# DIOT_Backplane.net
KiCad netlist of a schematic drawn in Altium Designer
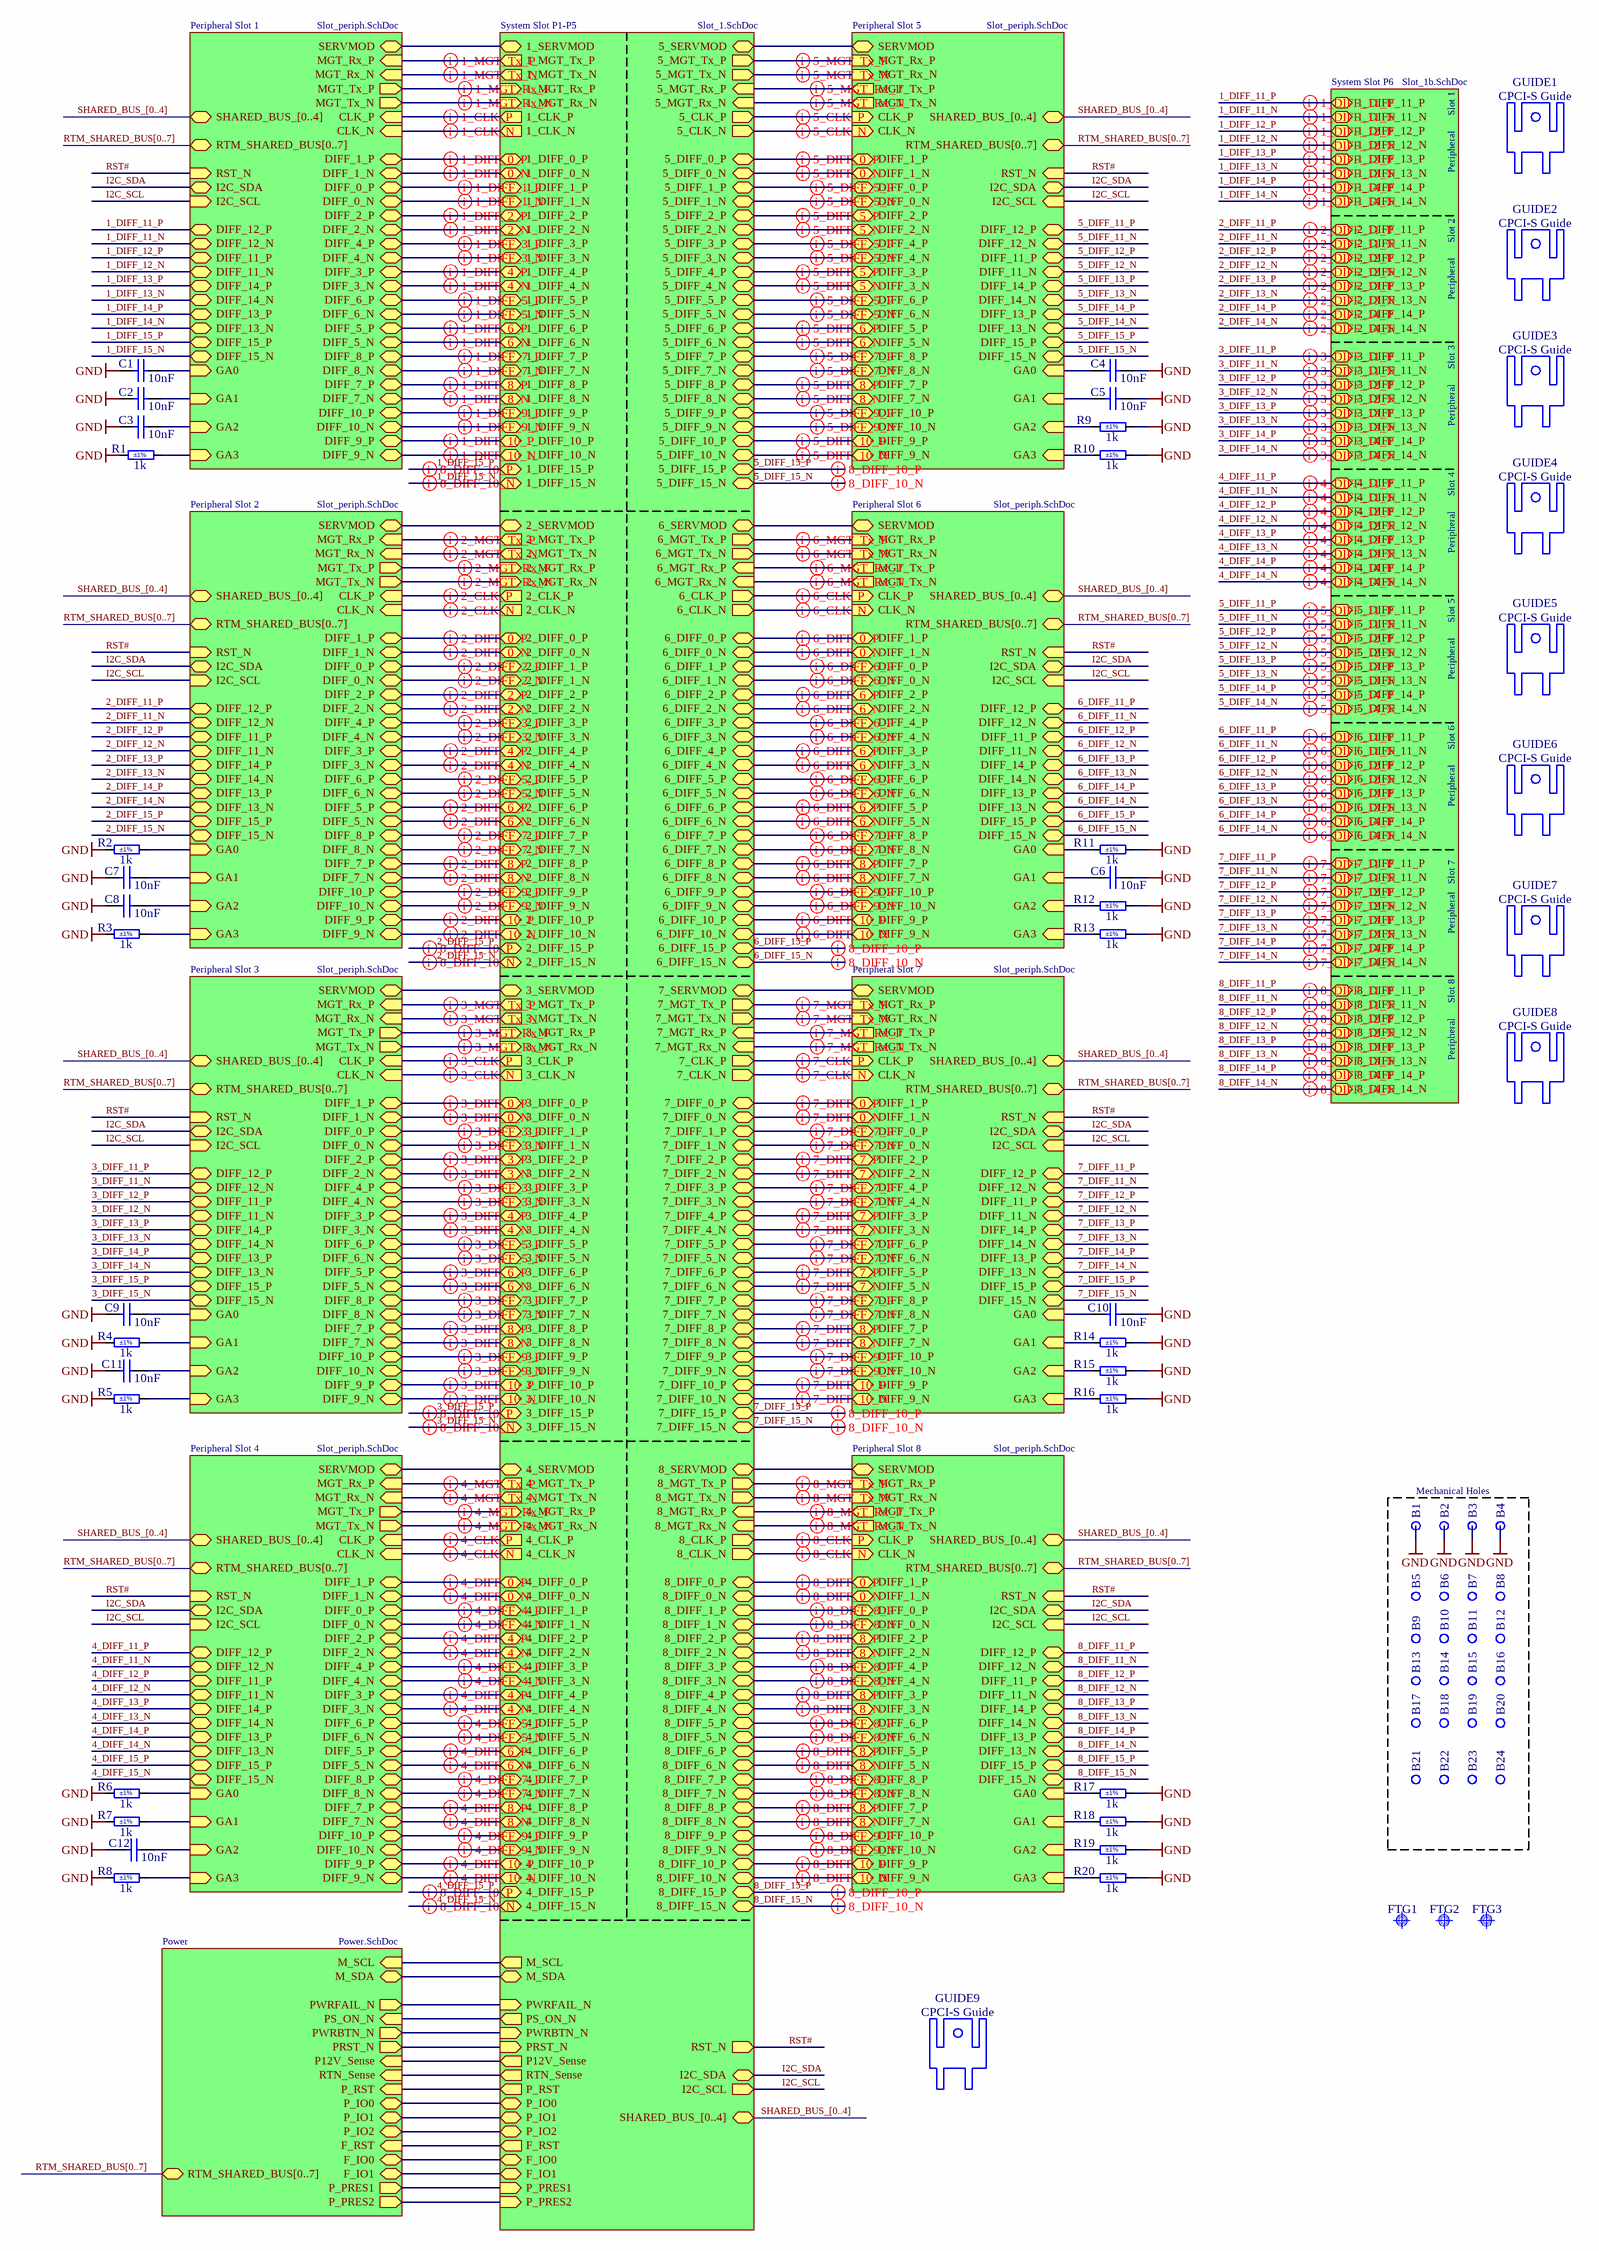
[diagram p0: DIOT_Backplane.SchDoc]

(export (version "E")
  (design (tool "Eeschema 10.0.6"))
  (components
    (comp (ref "B1")
      (value "Non Plated Hole")
      (footprint "MTG270_500_NPTH_8FCVIAS_BOTSM")
      (description "Single Terminal Socket")
      (fields
        (field (name "PART NUMBER") "NON-PLATED_HOLE2.7_PAD5.0_8FCVIAS_BOTSM")
        (field (name "AUTHOR") "CERN DEM WB")
      )
      (libsource (lib "Eletro-mechanical") (part "Single Terminal Socket"))
    )
    (comp (ref "B2")
      (value "Non Plated Hole")
      (footprint "MTG270_500_NPTH_8FCVIAS_BOTSM")
      (description "Single Terminal Socket")
      (fields
        (field (name "PART NUMBER") "NON-PLATED_HOLE2.7_PAD5.0_8FCVIAS_BOTSM")
        (field (name "AUTHOR") "CERN DEM WB")
      )
      (libsource (lib "Eletro-mechanical") (part "Single Terminal Socket"))
    )
    (comp (ref "B3")
      (value "Non Plated Hole")
      (footprint "MTG270_500_NPTH_8FCVIAS_BOTSM")
      (description "Single Terminal Socket")
      (fields
        (field (name "PART NUMBER") "NON-PLATED_HOLE2.7_PAD5.0_8FCVIAS_BOTSM")
        (field (name "AUTHOR") "CERN DEM WB")
      )
      (libsource (lib "Eletro-mechanical") (part "Single Terminal Socket"))
    )
    (comp (ref "B4")
      (value "Non Plated Hole")
      (footprint "MTG270_500_NPTH_8FCVIAS_BOTSM")
      (description "Single Terminal Socket")
      (fields
        (field (name "PART NUMBER") "NON-PLATED_HOLE2.7_PAD5.0_8FCVIAS_BOTSM")
        (field (name "AUTHOR") "CERN DEM WB")
      )
      (libsource (lib "Eletro-mechanical") (part "Single Terminal Socket"))
    )
    (comp (ref "B5")
      (value "Non Plated Hole")
      (footprint "MTG270")
      (description "Single Terminal Socket")
      (fields (field (name "PART NUMBER") "NON-PLATED_HOLE2.7") (field (name "AUTHOR") "CERN DEM BC"))
      (libsource (lib "Eletro-mechanical") (part "Single Terminal Socket"))
    )
    (comp (ref "B6")
      (value "Non Plated Hole")
      (footprint "MTG270")
      (description "Single Terminal Socket")
      (fields (field (name "PART NUMBER") "NON-PLATED_HOLE2.7") (field (name "AUTHOR") "CERN DEM BC"))
      (libsource (lib "Eletro-mechanical") (part "Single Terminal Socket"))
    )
    (comp (ref "B7")
      (value "Non Plated Hole")
      (footprint "MTG270")
      (description "Single Terminal Socket")
      (fields (field (name "PART NUMBER") "NON-PLATED_HOLE2.7") (field (name "AUTHOR") "CERN DEM BC"))
      (libsource (lib "Eletro-mechanical") (part "Single Terminal Socket"))
    )
    (comp (ref "B8")
      (value "Non Plated Hole")
      (footprint "MTG270")
      (description "Single Terminal Socket")
      (fields (field (name "PART NUMBER") "NON-PLATED_HOLE2.7") (field (name "AUTHOR") "CERN DEM BC"))
      (libsource (lib "Eletro-mechanical") (part "Single Terminal Socket"))
    )
    (comp (ref "B9")
      (value "Non Plated Hole")
      (footprint "MTG270")
      (description "Single Terminal Socket")
      (fields (field (name "PART NUMBER") "NON-PLATED_HOLE2.7") (field (name "AUTHOR") "CERN DEM BC"))
      (libsource (lib "Eletro-mechanical") (part "Single Terminal Socket"))
    )
    (comp (ref "B10")
      (value "Non Plated Hole")
      (footprint "MTG270")
      (description "Single Terminal Socket")
      (fields (field (name "PART NUMBER") "NON-PLATED_HOLE2.7") (field (name "AUTHOR") "CERN DEM BC"))
      (libsource (lib "Eletro-mechanical") (part "Single Terminal Socket"))
    )
    (comp (ref "B11")
      (value "Non Plated Hole")
      (footprint "MTG270")
      (description "Single Terminal Socket")
      (fields (field (name "PART NUMBER") "NON-PLATED_HOLE2.7") (field (name "AUTHOR") "CERN DEM BC"))
      (libsource (lib "Eletro-mechanical") (part "Single Terminal Socket"))
    )
    (comp (ref "B12")
      (value "Non Plated Hole")
      (footprint "MTG270")
      (description "Single Terminal Socket")
      (fields (field (name "PART NUMBER") "NON-PLATED_HOLE2.7") (field (name "AUTHOR") "CERN DEM BC"))
      (libsource (lib "Eletro-mechanical") (part "Single Terminal Socket"))
    )
    (comp (ref "B13")
      (value "Non Plated Hole")
      (footprint "MTG270")
      (description "Single Terminal Socket")
      (fields (field (name "PART NUMBER") "NON-PLATED_HOLE2.7") (field (name "AUTHOR") "CERN DEM BC"))
      (libsource (lib "Eletro-mechanical") (part "Single Terminal Socket"))
    )
    (comp (ref "B14")
      (value "Non Plated Hole")
      (footprint "MTG270")
      (description "Single Terminal Socket")
      (fields (field (name "PART NUMBER") "NON-PLATED_HOLE2.7") (field (name "AUTHOR") "CERN DEM BC"))
      (libsource (lib "Eletro-mechanical") (part "Single Terminal Socket"))
    )
    (comp (ref "B15")
      (value "Non Plated Hole")
      (footprint "MTG270")
      (description "Single Terminal Socket")
      (fields (field (name "PART NUMBER") "NON-PLATED_HOLE2.7") (field (name "AUTHOR") "CERN DEM BC"))
      (libsource (lib "Eletro-mechanical") (part "Single Terminal Socket"))
    )
    (comp (ref "B16")
      (value "Non Plated Hole")
      (footprint "MTG270")
      (description "Single Terminal Socket")
      (fields (field (name "PART NUMBER") "NON-PLATED_HOLE2.7") (field (name "AUTHOR") "CERN DEM BC"))
      (libsource (lib "Eletro-mechanical") (part "Single Terminal Socket"))
    )
    (comp (ref "B17")
      (value "Non Plated Hole")
      (footprint "MTG270")
      (description "Single Terminal Socket")
      (fields (field (name "PART NUMBER") "NON-PLATED_HOLE2.7") (field (name "AUTHOR") "CERN DEM BC"))
      (libsource (lib "Eletro-mechanical") (part "Single Terminal Socket"))
    )
    (comp (ref "B18")
      (value "Non Plated Hole")
      (footprint "MTG270")
      (description "Single Terminal Socket")
      (fields (field (name "PART NUMBER") "NON-PLATED_HOLE2.7") (field (name "AUTHOR") "CERN DEM BC"))
      (libsource (lib "Eletro-mechanical") (part "Single Terminal Socket"))
    )
    (comp (ref "B19")
      (value "Non Plated Hole")
      (footprint "MTG270")
      (description "Single Terminal Socket")
      (fields (field (name "PART NUMBER") "NON-PLATED_HOLE2.7") (field (name "AUTHOR") "CERN DEM BC"))
      (libsource (lib "Eletro-mechanical") (part "Single Terminal Socket"))
    )
    (comp (ref "B20")
      (value "Non Plated Hole")
      (footprint "MTG270")
      (description "Single Terminal Socket")
      (fields (field (name "PART NUMBER") "NON-PLATED_HOLE2.7") (field (name "AUTHOR") "CERN DEM BC"))
      (libsource (lib "Eletro-mechanical") (part "Single Terminal Socket"))
    )
    (comp (ref "B21")
      (value "Non Plated Hole")
      (footprint "MTG270")
      (description "Single Terminal Socket")
      (fields (field (name "PART NUMBER") "NON-PLATED_HOLE2.7") (field (name "AUTHOR") "CERN DEM BC"))
      (libsource (lib "Eletro-mechanical") (part "Single Terminal Socket"))
    )
    (comp (ref "B22")
      (value "Non Plated Hole")
      (footprint "MTG270")
      (description "Single Terminal Socket")
      (fields (field (name "PART NUMBER") "NON-PLATED_HOLE2.7") (field (name "AUTHOR") "CERN DEM BC"))
      (libsource (lib "Eletro-mechanical") (part "Single Terminal Socket"))
    )
    (comp (ref "B23")
      (value "Non Plated Hole")
      (footprint "MTG270")
      (description "Single Terminal Socket")
      (fields (field (name "PART NUMBER") "NON-PLATED_HOLE2.7") (field (name "AUTHOR") "CERN DEM BC"))
      (libsource (lib "Eletro-mechanical") (part "Single Terminal Socket"))
    )
    (comp (ref "B24")
      (value "Non Plated Hole")
      (footprint "MTG270")
      (description "Single Terminal Socket")
      (fields (field (name "PART NUMBER") "NON-PLATED_HOLE2.7") (field (name "AUTHOR") "CERN DEM BC"))
      (libsource (lib "Eletro-mechanical") (part "Single Terminal Socket"))
    )
    (comp (ref "C1")
      (value "10nF")
      (footprint "CAPC1005X55N")
      (description "Non-polarised capacitor")
      (fields
        (field (name "PART NUMBER") "CC0402_10NF_16V_10%_X7R")
        (field (name "VOLTAGE") "16V")
        (field (name "AUTHOR") "CERN DEM JLC")
      )
      (libsource (lib "Capacitors") (part "Capacitor - non polarized"))
    )
    (comp (ref "C2")
      (value "10nF")
      (footprint "CAPC1005X55N")
      (description "Non-polarised capacitor")
      (fields
        (field (name "PART NUMBER") "CC0402_10NF_16V_10%_X7R")
        (field (name "VOLTAGE") "16V")
        (field (name "AUTHOR") "CERN DEM JLC")
      )
      (libsource (lib "Capacitors") (part "Capacitor - non polarized"))
    )
    (comp (ref "C3")
      (value "10nF")
      (footprint "CAPC1005X55N")
      (description "Non-polarised capacitor")
      (fields
        (field (name "PART NUMBER") "CC0402_10NF_16V_10%_X7R")
        (field (name "VOLTAGE") "16V")
        (field (name "AUTHOR") "CERN DEM JLC")
      )
      (libsource (lib "Capacitors") (part "Capacitor - non polarized"))
    )
    (comp (ref "C4")
      (value "10nF")
      (footprint "CAPC1005X55N")
      (description "Non-polarised capacitor")
      (fields
        (field (name "PART NUMBER") "CC0402_10NF_16V_10%_X7R")
        (field (name "VOLTAGE") "16V")
        (field (name "AUTHOR") "CERN DEM JLC")
      )
      (libsource (lib "Capacitors") (part "Capacitor - non polarized"))
    )
    (comp (ref "C5")
      (value "10nF")
      (footprint "CAPC1005X55N")
      (description "Non-polarised capacitor")
      (fields
        (field (name "PART NUMBER") "CC0402_10NF_16V_10%_X7R")
        (field (name "VOLTAGE") "16V")
        (field (name "AUTHOR") "CERN DEM JLC")
      )
      (libsource (lib "Capacitors") (part "Capacitor - non polarized"))
    )
    (comp (ref "C6")
      (value "10nF")
      (footprint "CAPC1005X55N")
      (description "Non-polarised capacitor")
      (fields
        (field (name "PART NUMBER") "CC0402_10NF_16V_10%_X7R")
        (field (name "VOLTAGE") "16V")
        (field (name "AUTHOR") "CERN DEM JLC")
      )
      (libsource (lib "Capacitors") (part "Capacitor - non polarized"))
    )
    (comp (ref "C7")
      (value "10nF")
      (footprint "CAPC1005X55N")
      (description "Non-polarised capacitor")
      (fields
        (field (name "PART NUMBER") "CC0402_10NF_16V_10%_X7R")
        (field (name "VOLTAGE") "16V")
        (field (name "AUTHOR") "CERN DEM JLC")
      )
      (libsource (lib "Capacitors") (part "Capacitor - non polarized"))
    )
    (comp (ref "C8")
      (value "10nF")
      (footprint "CAPC1005X55N")
      (description "Non-polarised capacitor")
      (fields
        (field (name "PART NUMBER") "CC0402_10NF_16V_10%_X7R")
        (field (name "VOLTAGE") "16V")
        (field (name "AUTHOR") "CERN DEM JLC")
      )
      (libsource (lib "Capacitors") (part "Capacitor - non polarized"))
    )
    (comp (ref "C9")
      (value "10nF")
      (footprint "CAPC1005X55N")
      (description "Non-polarised capacitor")
      (fields
        (field (name "PART NUMBER") "CC0402_10NF_16V_10%_X7R")
        (field (name "VOLTAGE") "16V")
        (field (name "AUTHOR") "CERN DEM JLC")
      )
      (libsource (lib "Capacitors") (part "Capacitor - non polarized"))
    )
    (comp (ref "C10")
      (value "10nF")
      (footprint "CAPC1005X55N")
      (description "Non-polarised capacitor")
      (fields
        (field (name "PART NUMBER") "CC0402_10NF_16V_10%_X7R")
        (field (name "VOLTAGE") "16V")
        (field (name "AUTHOR") "CERN DEM JLC")
      )
      (libsource (lib "Capacitors") (part "Capacitor - non polarized"))
    )
    (comp (ref "C11")
      (value "10nF")
      (footprint "CAPC1005X55N")
      (description "Non-polarised capacitor")
      (fields
        (field (name "PART NUMBER") "CC0402_10NF_16V_10%_X7R")
        (field (name "VOLTAGE") "16V")
        (field (name "AUTHOR") "CERN DEM JLC")
      )
      (libsource (lib "Capacitors") (part "Capacitor - non polarized"))
    )
    (comp (ref "C12")
      (value "10nF")
      (footprint "CAPC1005X55N")
      (description "Non-polarised capacitor")
      (fields
        (field (name "PART NUMBER") "CC0402_10NF_16V_10%_X7R")
        (field (name "VOLTAGE") "16V")
        (field (name "AUTHOR") "CERN DEM JLC")
      )
      (libsource (lib "Capacitors") (part "Capacitor - non polarized"))
    )
    (comp (ref "FTG1")
      (value "Use only in PCB")
      (footprint "FIDUCIAL_TOP_C100-200")
      (description "Fiducial Target")
      (fields (field (name "PART NUMBER") "FIDUCIAL_TARGET_C100-200") (field (name "AUTHOR") "CERN DEM JLC"))
      (libsource (lib "Eletro-mechanical") (part "Fiducial Target"))
    )
    (comp (ref "FTG2")
      (value "Use only in PCB")
      (footprint "FIDUCIAL_TOP_C100-200")
      (description "Fiducial Target")
      (fields (field (name "PART NUMBER") "FIDUCIAL_TARGET_C100-200") (field (name "AUTHOR") "CERN DEM JLC"))
      (libsource (lib "Eletro-mechanical") (part "Fiducial Target"))
    )
    (comp (ref "FTG3")
      (value "Use only in PCB")
      (footprint "FIDUCIAL_TOP_C100-200")
      (description "Fiducial Target")
      (fields (field (name "PART NUMBER") "FIDUCIAL_TARGET_C100-200") (field (name "AUTHOR") "CERN DEM JLC"))
      (libsource (lib "Eletro-mechanical") (part "Fiducial Target"))
    )
    (comp (ref "GUIDE1")
      (value "CPCI-S Guide")
      (footprint "EDA-04126-V1-0")
      (description "PICMG CompactPCI Serial Backplane Guide Element")
      (fields
        (field (name "PART NUMBER") "EDA-04126-V1-0")
        (field (name "MANUFACTURER") "CERN")
        (field (name "AUTHOR") "CERN DEM BC")
      )
      (libsource (lib "Eletro-mechanical") (part "CPCI-S Guide"))
    )
    (comp (ref "GUIDE2")
      (value "CPCI-S Guide")
      (footprint "EDA-04126-V1-0")
      (description "PICMG CompactPCI Serial Backplane Guide Element")
      (fields
        (field (name "PART NUMBER") "EDA-04126-V1-0")
        (field (name "MANUFACTURER") "CERN")
        (field (name "AUTHOR") "CERN DEM BC")
      )
      (libsource (lib "Eletro-mechanical") (part "CPCI-S Guide"))
    )
    (comp (ref "GUIDE3")
      (value "CPCI-S Guide")
      (footprint "EDA-04126-V1-0")
      (description "PICMG CompactPCI Serial Backplane Guide Element")
      (fields
        (field (name "PART NUMBER") "EDA-04126-V1-0")
        (field (name "MANUFACTURER") "CERN")
        (field (name "AUTHOR") "CERN DEM BC")
      )
      (libsource (lib "Eletro-mechanical") (part "CPCI-S Guide"))
    )
    (comp (ref "GUIDE4")
      (value "CPCI-S Guide")
      (footprint "EDA-04126-V1-0")
      (description "PICMG CompactPCI Serial Backplane Guide Element")
      (fields
        (field (name "PART NUMBER") "EDA-04126-V1-0")
        (field (name "MANUFACTURER") "CERN")
        (field (name "AUTHOR") "CERN DEM BC")
      )
      (libsource (lib "Eletro-mechanical") (part "CPCI-S Guide"))
    )
    (comp (ref "GUIDE5")
      (value "CPCI-S Guide")
      (footprint "EDA-04126-V1-0")
      (description "PICMG CompactPCI Serial Backplane Guide Element")
      (fields
        (field (name "PART NUMBER") "EDA-04126-V1-0")
        (field (name "MANUFACTURER") "CERN")
        (field (name "AUTHOR") "CERN DEM BC")
      )
      (libsource (lib "Eletro-mechanical") (part "CPCI-S Guide"))
    )
    (comp (ref "GUIDE6")
      (value "CPCI-S Guide")
      (footprint "EDA-04126-V1-0")
      (description "PICMG CompactPCI Serial Backplane Guide Element")
      (fields
        (field (name "PART NUMBER") "EDA-04126-V1-0")
        (field (name "MANUFACTURER") "CERN")
        (field (name "AUTHOR") "CERN DEM BC")
      )
      (libsource (lib "Eletro-mechanical") (part "CPCI-S Guide"))
    )
    (comp (ref "GUIDE7")
      (value "CPCI-S Guide")
      (footprint "EDA-04126-V1-0")
      (description "PICMG CompactPCI Serial Backplane Guide Element")
      (fields
        (field (name "PART NUMBER") "EDA-04126-V1-0")
        (field (name "MANUFACTURER") "CERN")
        (field (name "AUTHOR") "CERN DEM BC")
      )
      (libsource (lib "Eletro-mechanical") (part "CPCI-S Guide"))
    )
    (comp (ref "GUIDE8")
      (value "CPCI-S Guide")
      (footprint "EDA-04126-V1-0")
      (description "PICMG CompactPCI Serial Backplane Guide Element")
      (fields
        (field (name "PART NUMBER") "EDA-04126-V1-0")
        (field (name "MANUFACTURER") "CERN")
        (field (name "AUTHOR") "CERN DEM BC")
      )
      (libsource (lib "Eletro-mechanical") (part "CPCI-S Guide"))
    )
    (comp (ref "GUIDE9")
      (value "CPCI-S Guide")
      (footprint "EDA-04126-V1-0")
      (description "PICMG CompactPCI Serial Backplane Guide Element")
      (fields
        (field (name "PART NUMBER") "EDA-04126-V1-0")
        (field (name "MANUFACTURER") "CERN")
        (field (name "AUTHOR") "CERN DEM BC")
      )
      (libsource (lib "Eletro-mechanical") (part "CPCI-S Guide"))
    )
    (comp (ref "R1")
      (value "1k")
      (footprint "RESC1005X40N")
      (description "Resistor - 1%")
      (fields
        (field (name "TOLERANCE") "±1%")
        (field (name "PART NUMBER") "R0402_1K_1%_0.0625W_100PPM")
        (field (name "POWER") "0.0625W")
        (field (name "AUTHOR") "CERN DEM JLC")
      )
      (libsource (lib "Resistors") (part "Resistor - 1%"))
    )
    (comp (ref "R2")
      (value "1k")
      (footprint "RESC1005X40N")
      (description "Resistor - 1%")
      (fields
        (field (name "TOLERANCE") "±1%")
        (field (name "PART NUMBER") "R0402_1K_1%_0.0625W_100PPM")
        (field (name "POWER") "0.0625W")
        (field (name "AUTHOR") "CERN DEM JLC")
      )
      (libsource (lib "Resistors") (part "Resistor - 1%"))
    )
    (comp (ref "R3")
      (value "1k")
      (footprint "RESC1005X40N")
      (description "Resistor - 1%")
      (fields
        (field (name "TOLERANCE") "±1%")
        (field (name "PART NUMBER") "R0402_1K_1%_0.0625W_100PPM")
        (field (name "POWER") "0.0625W")
        (field (name "AUTHOR") "CERN DEM JLC")
      )
      (libsource (lib "Resistors") (part "Resistor - 1%"))
    )
    (comp (ref "R4")
      (value "1k")
      (footprint "RESC1005X40N")
      (description "Resistor - 1%")
      (fields
        (field (name "TOLERANCE") "±1%")
        (field (name "PART NUMBER") "R0402_1K_1%_0.0625W_100PPM")
        (field (name "POWER") "0.0625W")
        (field (name "AUTHOR") "CERN DEM JLC")
      )
      (libsource (lib "Resistors") (part "Resistor - 1%"))
    )
    (comp (ref "R5")
      (value "1k")
      (footprint "RESC1005X40N")
      (description "Resistor - 1%")
      (fields
        (field (name "TOLERANCE") "±1%")
        (field (name "PART NUMBER") "R0402_1K_1%_0.0625W_100PPM")
        (field (name "POWER") "0.0625W")
        (field (name "AUTHOR") "CERN DEM JLC")
      )
      (libsource (lib "Resistors") (part "Resistor - 1%"))
    )
    (comp (ref "R6")
      (value "1k")
      (footprint "RESC1005X40N")
      (description "Resistor - 1%")
      (fields
        (field (name "TOLERANCE") "±1%")
        (field (name "PART NUMBER") "R0402_1K_1%_0.0625W_100PPM")
        (field (name "POWER") "0.0625W")
        (field (name "AUTHOR") "CERN DEM JLC")
      )
      (libsource (lib "Resistors") (part "Resistor - 1%"))
    )
    (comp (ref "R7")
      (value "1k")
      (footprint "RESC1005X40N")
      (description "Resistor - 1%")
      (fields
        (field (name "TOLERANCE") "±1%")
        (field (name "PART NUMBER") "R0402_1K_1%_0.0625W_100PPM")
        (field (name "POWER") "0.0625W")
        (field (name "AUTHOR") "CERN DEM JLC")
      )
      (libsource (lib "Resistors") (part "Resistor - 1%"))
    )
    (comp (ref "R8")
      (value "1k")
      (footprint "RESC1005X40N")
      (description "Resistor - 1%")
      (fields
        (field (name "TOLERANCE") "±1%")
        (field (name "PART NUMBER") "R0402_1K_1%_0.0625W_100PPM")
        (field (name "POWER") "0.0625W")
        (field (name "AUTHOR") "CERN DEM JLC")
      )
      (libsource (lib "Resistors") (part "Resistor - 1%"))
    )
    (comp (ref "R9")
      (value "1k")
      (footprint "RESC1005X40N")
      (description "Resistor - 1%")
      (fields
        (field (name "TOLERANCE") "±1%")
        (field (name "PART NUMBER") "R0402_1K_1%_0.0625W_100PPM")
        (field (name "POWER") "0.0625W")
        (field (name "AUTHOR") "CERN DEM JLC")
      )
      (libsource (lib "Resistors") (part "Resistor - 1%"))
    )
    (comp (ref "R10")
      (value "1k")
      (footprint "RESC1005X40N")
      (description "Resistor - 1%")
      (fields
        (field (name "TOLERANCE") "±1%")
        (field (name "PART NUMBER") "R0402_1K_1%_0.0625W_100PPM")
        (field (name "POWER") "0.0625W")
        (field (name "AUTHOR") "CERN DEM JLC")
      )
      (libsource (lib "Resistors") (part "Resistor - 1%"))
    )
    (comp (ref "R11")
      (value "1k")
      (footprint "RESC1005X40N")
      (description "Resistor - 1%")
      (fields
        (field (name "TOLERANCE") "±1%")
        (field (name "PART NUMBER") "R0402_1K_1%_0.0625W_100PPM")
        (field (name "POWER") "0.0625W")
        (field (name "AUTHOR") "CERN DEM JLC")
      )
      (libsource (lib "Resistors") (part "Resistor - 1%"))
    )
    (comp (ref "R12")
      (value "1k")
      (footprint "RESC1005X40N")
      (description "Resistor - 1%")
      (fields
        (field (name "TOLERANCE") "±1%")
        (field (name "PART NUMBER") "R0402_1K_1%_0.0625W_100PPM")
        (field (name "POWER") "0.0625W")
        (field (name "AUTHOR") "CERN DEM JLC")
      )
      (libsource (lib "Resistors") (part "Resistor - 1%"))
    )
    (comp (ref "R13")
      (value "1k")
      (footprint "RESC1005X40N")
      (description "Resistor - 1%")
      (fields
        (field (name "TOLERANCE") "±1%")
        (field (name "PART NUMBER") "R0402_1K_1%_0.0625W_100PPM")
        (field (name "POWER") "0.0625W")
        (field (name "AUTHOR") "CERN DEM JLC")
      )
      (libsource (lib "Resistors") (part "Resistor - 1%"))
    )
    (comp (ref "R14")
      (value "1k")
      (footprint "RESC1005X40N")
      (description "Resistor - 1%")
      (fields
        (field (name "TOLERANCE") "±1%")
        (field (name "PART NUMBER") "R0402_1K_1%_0.0625W_100PPM")
        (field (name "POWER") "0.0625W")
        (field (name "AUTHOR") "CERN DEM JLC")
      )
      (libsource (lib "Resistors") (part "Resistor - 1%"))
    )
    (comp (ref "R15")
      (value "1k")
      (footprint "RESC1005X40N")
      (description "Resistor - 1%")
      (fields
        (field (name "TOLERANCE") "±1%")
        (field (name "PART NUMBER") "R0402_1K_1%_0.0625W_100PPM")
        (field (name "POWER") "0.0625W")
        (field (name "AUTHOR") "CERN DEM JLC")
      )
      (libsource (lib "Resistors") (part "Resistor - 1%"))
    )
    (comp (ref "R16")
      (value "1k")
      (footprint "RESC1005X40N")
      (description "Resistor - 1%")
      (fields
        (field (name "TOLERANCE") "±1%")
        (field (name "PART NUMBER") "R0402_1K_1%_0.0625W_100PPM")
        (field (name "POWER") "0.0625W")
        (field (name "AUTHOR") "CERN DEM JLC")
      )
      (libsource (lib "Resistors") (part "Resistor - 1%"))
    )
    (comp (ref "R17")
      (value "1k")
      (footprint "RESC1005X40N")
      (description "Resistor - 1%")
      (fields
        (field (name "TOLERANCE") "±1%")
        (field (name "PART NUMBER") "R0402_1K_1%_0.0625W_100PPM")
        (field (name "POWER") "0.0625W")
        (field (name "AUTHOR") "CERN DEM JLC")
      )
      (libsource (lib "Resistors") (part "Resistor - 1%"))
    )
    (comp (ref "R18")
      (value "1k")
      (footprint "RESC1005X40N")
      (description "Resistor - 1%")
      (fields
        (field (name "TOLERANCE") "±1%")
        (field (name "PART NUMBER") "R0402_1K_1%_0.0625W_100PPM")
        (field (name "POWER") "0.0625W")
        (field (name "AUTHOR") "CERN DEM JLC")
      )
      (libsource (lib "Resistors") (part "Resistor - 1%"))
    )
    (comp (ref "R19")
      (value "1k")
      (footprint "RESC1005X40N")
      (description "Resistor - 1%")
      (fields
        (field (name "TOLERANCE") "±1%")
        (field (name "PART NUMBER") "R0402_1K_1%_0.0625W_100PPM")
        (field (name "POWER") "0.0625W")
        (field (name "AUTHOR") "CERN DEM JLC")
      )
      (libsource (lib "Resistors") (part "Resistor - 1%"))
    )
    (comp (ref "R20")
      (value "1k")
      (footprint "RESC1005X40N")
      (description "Resistor - 1%")
      (fields
        (field (name "TOLERANCE") "±1%")
        (field (name "PART NUMBER") "R0402_1K_1%_0.0625W_100PPM")
        (field (name "POWER") "0.0625W")
        (field (name "AUTHOR") "CERN DEM JLC")
      )
      (libsource (lib "Resistors") (part "Resistor - 1%"))
    )
  )
  (nets
    (net (code "313") (name "/GA0") (class "Default")
      (node (ref "C1") (pin "2") (pinfunction "2_2") (pintype "passive"))
    )
    (net (code "314") (name "/GA0_1") (class "Default")
      (node (ref "R17") (pin "1") (pinfunction "1_1") (pintype "passive"))
    )
    (net (code "315") (name "/GA0_2") (class "Default")
      (node (ref "R2") (pin "2") (pinfunction "2_2") (pintype "passive"))
    )
    (net (code "316") (name "/GA0_3") (class "Default")
      (node (ref "R6") (pin "2") (pinfunction "2_2") (pintype "passive"))
    )
    (net (code "317") (name "/GA0_4") (class "Default")
      (node (ref "C9") (pin "2") (pinfunction "2_2") (pintype "passive"))
    )
    (net (code "318") (name "/GA0_5") (class "Default")
      (node (ref "C4") (pin "1") (pinfunction "1_1") (pintype "passive"))
    )
    (net (code "319") (name "/GA0_6") (class "Default")
      (node (ref "R11") (pin "1") (pinfunction "1_1") (pintype "passive"))
    )
    (net (code "320") (name "/GA0_7") (class "Default")
      (node (ref "C10") (pin "1") (pinfunction "1_1") (pintype "passive"))
    )
    (net (code "321") (name "/GA1") (class "Default")
      (node (ref "C2") (pin "2") (pinfunction "2_2") (pintype "passive"))
    )
    (net (code "322") (name "/GA1_1") (class "Default")
      (node (ref "R18") (pin "1") (pinfunction "1_1") (pintype "passive"))
    )
    (net (code "323") (name "/GA1_2") (class "Default")
      (node (ref "C7") (pin "2") (pinfunction "2_2") (pintype "passive"))
    )
    (net (code "324") (name "/GA1_3") (class "Default")
      (node (ref "R7") (pin "2") (pinfunction "2_2") (pintype "passive"))
    )
    (net (code "325") (name "/GA1_4") (class "Default")
      (node (ref "R4") (pin "2") (pinfunction "2_2") (pintype "passive"))
    )
    (net (code "326") (name "/GA1_5") (class "Default")
      (node (ref "C5") (pin "1") (pinfunction "1_1") (pintype "passive"))
    )
    (net (code "327") (name "/GA1_6") (class "Default")
      (node (ref "C6") (pin "1") (pinfunction "1_1") (pintype "passive"))
    )
    (net (code "328") (name "/GA1_7") (class "Default")
      (node (ref "R14") (pin "1") (pinfunction "1_1") (pintype "passive"))
    )
    (net (code "329") (name "/GA2") (class "Default")
      (node (ref "C3") (pin "2") (pinfunction "2_2") (pintype "passive"))
    )
    (net (code "330") (name "/GA2_1") (class "Default")
      (node (ref "R19") (pin "1") (pinfunction "1_1") (pintype "passive"))
    )
    (net (code "331") (name "/GA2_2") (class "Default")
      (node (ref "C8") (pin "2") (pinfunction "2_2") (pintype "passive"))
    )
    (net (code "332") (name "/GA2_3") (class "Default")
      (node (ref "C12") (pin "2") (pinfunction "2_2") (pintype "passive"))
    )
    (net (code "333") (name "/GA2_4") (class "Default")
      (node (ref "C11") (pin "2") (pinfunction "2_2") (pintype "passive"))
    )
    (net (code "334") (name "/GA2_5") (class "Default")
      (node (ref "R9") (pin "1") (pinfunction "1_1") (pintype "passive"))
    )
    (net (code "335") (name "/GA2_6") (class "Default")
      (node (ref "R12") (pin "1") (pinfunction "1_1") (pintype "passive"))
    )
    (net (code "336") (name "/GA2_7") (class "Default")
      (node (ref "R15") (pin "1") (pinfunction "1_1") (pintype "passive"))
    )
    (net (code "337") (name "/GA3") (class "Default")
      (node (ref "R1") (pin "2") (pinfunction "2_2") (pintype "passive"))
    )
    (net (code "338") (name "/GA3_1") (class "Default")
      (node (ref "R20") (pin "1") (pinfunction "1_1") (pintype "passive"))
    )
    (net (code "339") (name "/GA3_2") (class "Default")
      (node (ref "R3") (pin "2") (pinfunction "2_2") (pintype "passive"))
    )
    (net (code "340") (name "/GA3_3") (class "Default")
      (node (ref "R8") (pin "2") (pinfunction "2_2") (pintype "passive"))
    )
    (net (code "341") (name "/GA3_4") (class "Default")
      (node (ref "R5") (pin "2") (pinfunction "2_2") (pintype "passive"))
    )
    (net (code "342") (name "/GA3_5") (class "Default")
      (node (ref "R10") (pin "1") (pinfunction "1_1") (pintype "passive"))
    )
    (net (code "343") (name "/GA3_6") (class "Default")
      (node (ref "R13") (pin "1") (pinfunction "1_1") (pintype "passive"))
    )
    (net (code "344") (name "/GA3_7") (class "Default")
      (node (ref "R16") (pin "1") (pinfunction "1_1") (pintype "passive"))
    )
    (net (code "380") (name "GND") (class "Default")
      (node (ref "B1") (pin "1") (pinfunction "1_1") (pintype "bidirectional"))
      (node (ref "B2") (pin "1") (pinfunction "1_1") (pintype "bidirectional"))
      (node (ref "B3") (pin "1") (pinfunction "1_1") (pintype "bidirectional"))
      (node (ref "B4") (pin "1") (pinfunction "1_1") (pintype "bidirectional"))
      (node (ref "C1") (pin "1") (pinfunction "1_1") (pintype "passive"))
      (node (ref "C10") (pin "2") (pinfunction "2_2") (pintype "passive"))
      (node (ref "C11") (pin "1") (pinfunction "1_1") (pintype "passive"))
      (node (ref "C12") (pin "1") (pinfunction "1_1") (pintype "passive"))
      (node (ref "C2") (pin "1") (pinfunction "1_1") (pintype "passive"))
      (node (ref "C3") (pin "1") (pinfunction "1_1") (pintype "passive"))
      (node (ref "C4") (pin "2") (pinfunction "2_2") (pintype "passive"))
      (node (ref "C5") (pin "2") (pinfunction "2_2") (pintype "passive"))
      (node (ref "C6") (pin "2") (pinfunction "2_2") (pintype "passive"))
      (node (ref "C7") (pin "1") (pinfunction "1_1") (pintype "passive"))
      (node (ref "C8") (pin "1") (pinfunction "1_1") (pintype "passive"))
      (node (ref "C9") (pin "1") (pinfunction "1_1") (pintype "passive"))
      (node (ref "R1") (pin "1") (pinfunction "1_1") (pintype "passive"))
      (node (ref "R10") (pin "2") (pinfunction "2_2") (pintype "passive"))
      (node (ref "R11") (pin "2") (pinfunction "2_2") (pintype "passive"))
      (node (ref "R12") (pin "2") (pinfunction "2_2") (pintype "passive"))
      (node (ref "R13") (pin "2") (pinfunction "2_2") (pintype "passive"))
      (node (ref "R14") (pin "2") (pinfunction "2_2") (pintype "passive"))
      (node (ref "R15") (pin "2") (pinfunction "2_2") (pintype "passive"))
      (node (ref "R16") (pin "2") (pinfunction "2_2") (pintype "passive"))
      (node (ref "R17") (pin "2") (pinfunction "2_2") (pintype "passive"))
      (node (ref "R18") (pin "2") (pinfunction "2_2") (pintype "passive"))
      (node (ref "R19") (pin "2") (pinfunction "2_2") (pintype "passive"))
      (node (ref "R2") (pin "1") (pinfunction "1_1") (pintype "passive"))
      (node (ref "R20") (pin "2") (pinfunction "2_2") (pintype "passive"))
      (node (ref "R3") (pin "1") (pinfunction "1_1") (pintype "passive"))
      (node (ref "R4") (pin "1") (pinfunction "1_1") (pintype "passive"))
      (node (ref "R5") (pin "1") (pinfunction "1_1") (pintype "passive"))
      (node (ref "R6") (pin "1") (pinfunction "1_1") (pintype "passive"))
      (node (ref "R7") (pin "1") (pinfunction "1_1") (pintype "passive"))
      (node (ref "R8") (pin "1") (pinfunction "1_1") (pintype "passive"))
      (node (ref "R9") (pin "2") (pinfunction "2_2") (pintype "passive"))
    )
    (net (code "381") (name "unconnected-(B5-Pad1)") (class "Default")
      (node (ref "B5") (pin "1") (pinfunction "1_1") (pintype "bidirectional"))
    )
    (net (code "382") (name "unconnected-(B6-Pad1)") (class "Default")
      (node (ref "B6") (pin "1") (pinfunction "1_1") (pintype "bidirectional"))
    )
    (net (code "383") (name "unconnected-(B7-Pad1)") (class "Default")
      (node (ref "B7") (pin "1") (pinfunction "1_1") (pintype "bidirectional"))
    )
    (net (code "384") (name "unconnected-(B8-Pad1)") (class "Default")
      (node (ref "B8") (pin "1") (pinfunction "1_1") (pintype "bidirectional"))
    )
    (net (code "385") (name "unconnected-(B9-Pad1)") (class "Default")
      (node (ref "B9") (pin "1") (pinfunction "1_1") (pintype "bidirectional"))
    )
    (net (code "386") (name "unconnected-(B10-Pad1)") (class "Default")
      (node (ref "B10") (pin "1") (pinfunction "1_1") (pintype "bidirectional"))
    )
    (net (code "387") (name "unconnected-(B11-Pad1)") (class "Default")
      (node (ref "B11") (pin "1") (pinfunction "1_1") (pintype "bidirectional"))
    )
    (net (code "388") (name "unconnected-(B12-Pad1)") (class "Default")
      (node (ref "B12") (pin "1") (pinfunction "1_1") (pintype "bidirectional"))
    )
    (net (code "389") (name "unconnected-(B13-Pad1)") (class "Default")
      (node (ref "B13") (pin "1") (pinfunction "1_1") (pintype "bidirectional"))
    )
    (net (code "390") (name "unconnected-(B14-Pad1)") (class "Default")
      (node (ref "B14") (pin "1") (pinfunction "1_1") (pintype "bidirectional"))
    )
    (net (code "391") (name "unconnected-(B15-Pad1)") (class "Default")
      (node (ref "B15") (pin "1") (pinfunction "1_1") (pintype "bidirectional"))
    )
    (net (code "392") (name "unconnected-(B16-Pad1)") (class "Default")
      (node (ref "B16") (pin "1") (pinfunction "1_1") (pintype "bidirectional"))
    )
    (net (code "393") (name "unconnected-(B17-Pad1)") (class "Default")
      (node (ref "B17") (pin "1") (pinfunction "1_1") (pintype "bidirectional"))
    )
    (net (code "394") (name "unconnected-(B18-Pad1)") (class "Default")
      (node (ref "B18") (pin "1") (pinfunction "1_1") (pintype "bidirectional"))
    )
    (net (code "395") (name "unconnected-(B19-Pad1)") (class "Default")
      (node (ref "B19") (pin "1") (pinfunction "1_1") (pintype "bidirectional"))
    )
    (net (code "396") (name "unconnected-(B20-Pad1)") (class "Default")
      (node (ref "B20") (pin "1") (pinfunction "1_1") (pintype "bidirectional"))
    )
    (net (code "397") (name "unconnected-(B21-Pad1)") (class "Default")
      (node (ref "B21") (pin "1") (pinfunction "1_1") (pintype "bidirectional"))
    )
    (net (code "398") (name "unconnected-(B22-Pad1)") (class "Default")
      (node (ref "B22") (pin "1") (pinfunction "1_1") (pintype "bidirectional"))
    )
    (net (code "399") (name "unconnected-(B23-Pad1)") (class "Default")
      (node (ref "B23") (pin "1") (pinfunction "1_1") (pintype "bidirectional"))
    )
    (net (code "400") (name "unconnected-(B24-Pad1)") (class "Default")
      (node (ref "B24") (pin "1") (pinfunction "1_1") (pintype "bidirectional"))
    )
    (net (code "401") (name "unconnected-(GUIDE1-Pad1)") (class "Default")
      (node (ref "GUIDE1") (pin "1") (pinfunction "1_1") (pintype "bidirectional"))
    )
    (net (code "402") (name "unconnected-(GUIDE2-Pad1)") (class "Default")
      (node (ref "GUIDE2") (pin "1") (pinfunction "1_1") (pintype "bidirectional"))
    )
    (net (code "403") (name "unconnected-(GUIDE3-Pad1)") (class "Default")
      (node (ref "GUIDE3") (pin "1") (pinfunction "1_1") (pintype "bidirectional"))
    )
    (net (code "404") (name "unconnected-(GUIDE4-Pad1)") (class "Default")
      (node (ref "GUIDE4") (pin "1") (pinfunction "1_1") (pintype "bidirectional"))
    )
    (net (code "405") (name "unconnected-(GUIDE5-Pad1)") (class "Default")
      (node (ref "GUIDE5") (pin "1") (pinfunction "1_1") (pintype "bidirectional"))
    )
    (net (code "406") (name "unconnected-(GUIDE6-Pad1)") (class "Default")
      (node (ref "GUIDE6") (pin "1") (pinfunction "1_1") (pintype "bidirectional"))
    )
    (net (code "407") (name "unconnected-(GUIDE7-Pad1)") (class "Default")
      (node (ref "GUIDE7") (pin "1") (pinfunction "1_1") (pintype "bidirectional"))
    )
    (net (code "408") (name "unconnected-(GUIDE8-Pad1)") (class "Default")
      (node (ref "GUIDE8") (pin "1") (pinfunction "1_1") (pintype "bidirectional"))
    )
    (net (code "409") (name "unconnected-(GUIDE9-Pad1)") (class "Default")
      (node (ref "GUIDE9") (pin "1") (pinfunction "1_1") (pintype "bidirectional"))
    )
  )
)
